# Adafruit_Speaker_Bonnet.net
KiCad netlist of a schematic drawn in EAGLE
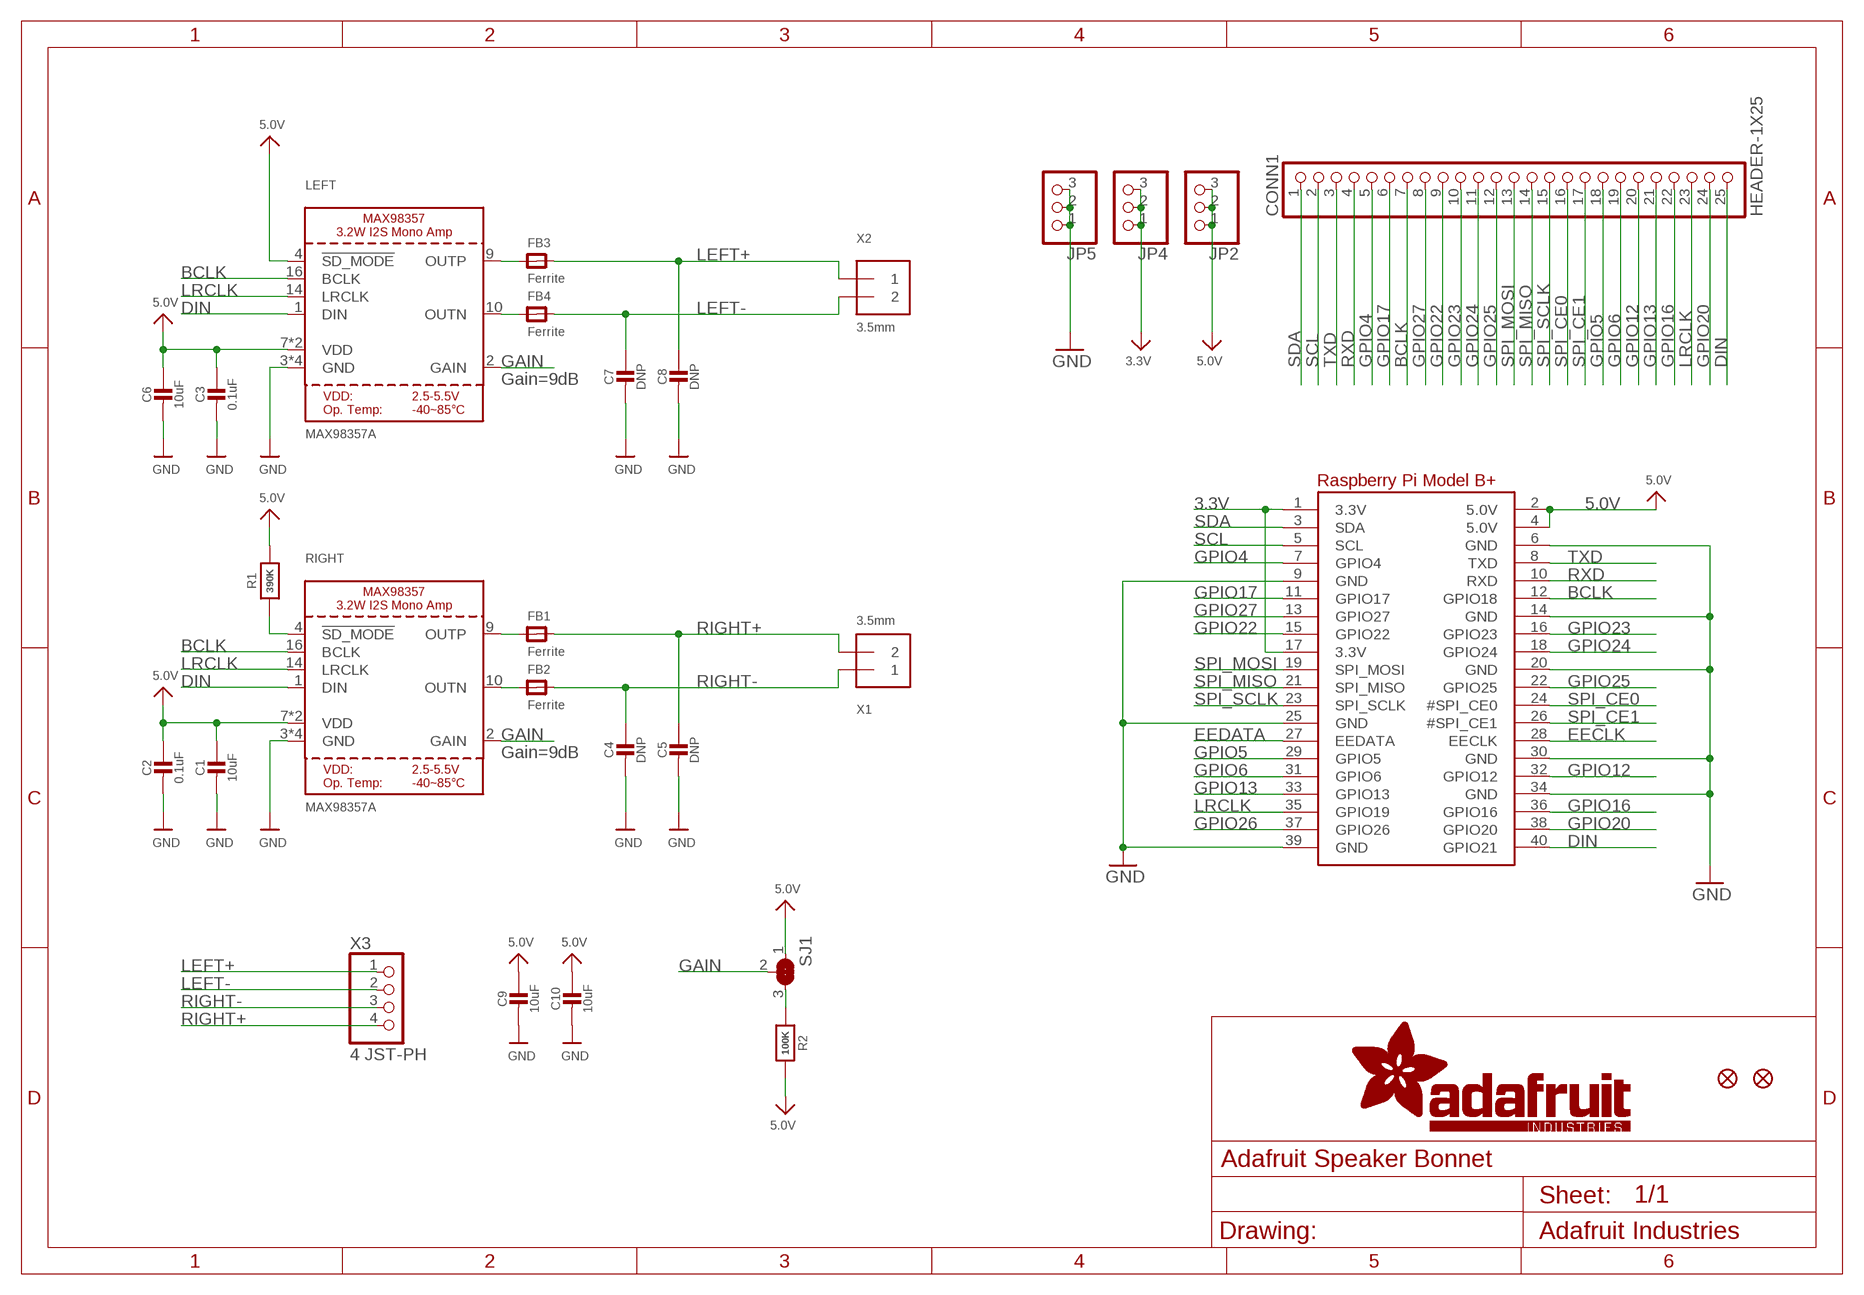
[diagram p0: schematic, sheet 1]

(export (version "E")
  (design (tool "Eeschema 10.0.6"))
  (components
    (comp (ref "C1")
      (value "10uF")
      (footprint "eagle-import:0805-NO")
      (libsource (lib "eagle-import") (part "CAP_CERAMIC0805-NOOUTLINE"))
    )
    (comp (ref "C2")
      (value "0.1uF")
      (footprint "eagle-import:0805-NO")
      (libsource (lib "eagle-import") (part "CAP_CERAMIC0805-NOOUTLINE"))
    )
    (comp (ref "C3")
      (value "0.1uF")
      (footprint "eagle-import:0805-NO")
      (libsource (lib "eagle-import") (part "CAP_CERAMIC0805-NOOUTLINE"))
    )
    (comp (ref "C4")
      (value "DNP")
      (footprint "eagle-import:0805-NO")
      (libsource (lib "eagle-import") (part "CAP_CERAMIC0805-NOOUTLINE"))
    )
    (comp (ref "C5")
      (value "DNP")
      (footprint "eagle-import:0805-NO")
      (libsource (lib "eagle-import") (part "CAP_CERAMIC0805-NOOUTLINE"))
    )
    (comp (ref "C6")
      (value "10uF")
      (footprint "eagle-import:0805-NO")
      (libsource (lib "eagle-import") (part "CAP_CERAMIC0805-NOOUTLINE"))
    )
    (comp (ref "C7")
      (value "DNP")
      (footprint "eagle-import:0805-NO")
      (libsource (lib "eagle-import") (part "CAP_CERAMIC0805-NOOUTLINE"))
    )
    (comp (ref "C8")
      (value "DNP")
      (footprint "eagle-import:0805-NO")
      (libsource (lib "eagle-import") (part "CAP_CERAMIC0805-NOOUTLINE"))
    )
    (comp (ref "C9")
      (value "10uF")
      (footprint "eagle-import:0805-NO")
      (libsource (lib "eagle-import") (part "CAP_CERAMIC0805-NOOUTLINE"))
    )
    (comp (ref "C10")
      (value "10uF")
      (footprint "eagle-import:0805-NO")
      (libsource (lib "eagle-import") (part "CAP_CERAMIC0805-NOOUTLINE"))
    )
    (comp (ref "CONN1")
      (value "HEADER-1X25")
      (footprint "eagle-import:1X25_ROUND_70MIL")
      (libsource (lib "eagle-import") (part "HEADER-1X25"))
    )
    (comp (ref "FB1")
      (value "Ferrite")
      (footprint "eagle-import:0805-NO")
      (libsource (lib "eagle-import") (part "FERRITE-0805NO"))
    )
    (comp (ref "FB2")
      (value "Ferrite")
      (footprint "eagle-import:0805-NO")
      (libsource (lib "eagle-import") (part "FERRITE-0805NO"))
    )
    (comp (ref "FB3")
      (value "Ferrite")
      (footprint "eagle-import:0805-NO")
      (libsource (lib "eagle-import") (part "FERRITE-0805NO"))
    )
    (comp (ref "FB4")
      (value "Ferrite")
      (footprint "eagle-import:0805-NO")
      (libsource (lib "eagle-import") (part "FERRITE-0805NO"))
    )
    (comp (ref "FID1")
      (value "FIDUCIAL\"\"")
      (footprint "eagle-import:FIDUCIAL_1MM")
      (libsource (lib "eagle-import") (part "FIDUCIAL{dblquote}{dblquote}"))
    )
    (comp (ref "FID2")
      (value "FIDUCIAL\"\"")
      (footprint "eagle-import:FIDUCIAL_1MM")
      (libsource (lib "eagle-import") (part "FIDUCIAL{dblquote}{dblquote}"))
    )
    (comp (ref "JP2")
      (value "HEADER-1X376MIL")
      (footprint "eagle-import:1X03_ROUND_76")
      (libsource (lib "eagle-import") (part "HEADER-1X376MIL"))
    )
    (comp (ref "JP4")
      (value "HEADER-1X376MIL")
      (footprint "eagle-import:1X03_ROUND_76")
      (libsource (lib "eagle-import") (part "HEADER-1X376MIL"))
    )
    (comp (ref "JP5")
      (value "HEADER-1X376MIL")
      (footprint "eagle-import:1X03_ROUND_76")
      (libsource (lib "eagle-import") (part "HEADER-1X376MIL"))
    )
    (comp (ref "LEFT")
      (value "MAX98357A")
      (footprint "eagle-import:QFN16_3MM")
      (libsource (lib "eagle-import") (part "AUDIOAMP_MAX98357"))
    )
    (comp (ref "R1")
      (value "390K")
      (footprint "eagle-import:0805-NO")
      (libsource (lib "eagle-import") (part "RESISTOR0805_NOOUTLINE"))
    )
    (comp (ref "R2")
      (value "100K")
      (footprint "eagle-import:0805-NO")
      (libsource (lib "eagle-import") (part "RESISTOR0805_NOOUTLINE"))
    )
    (comp (ref "RIGHT")
      (value "MAX98357A")
      (footprint "eagle-import:QFN16_3MM")
      (libsource (lib "eagle-import") (part "AUDIOAMP_MAX98357"))
    )
    (comp (ref "RPI1")
      (value "RASPBERRYPI_BPLUS_BONNETNODIM")
      (footprint "eagle-import:PI_BONNET_NODIM")
      (libsource (lib "eagle-import") (part "RASPBERRYPI_BPLUS_BONNETNODIM"))
    )
    (comp (ref "SJ1")
      (value "SOLDERJUMPER_2WAY")
      (footprint "eagle-import:SOLDERJUMPER_2WAY_OPEN_NOPASTE")
      (libsource (lib "eagle-import") (part "SOLDERJUMPER_2WAY"))
    )
    (comp (ref "X1")
      (value "3.5mm")
      (footprint "eagle-import:TERMBLOCK_1X2-3.5MM")
      (libsource (lib "eagle-import") (part "TERMBLOCK_1X2"))
    )
    (comp (ref "X2")
      (value "3.5mm")
      (footprint "eagle-import:TERMBLOCK_1X2-3.5MM")
      (libsource (lib "eagle-import") (part "TERMBLOCK_1X2"))
    )
    (comp (ref "X3")
      (value "4 JST-PH")
      (footprint "eagle-import:JSTPH4")
      (libsource (lib "eagle-import") (part "CON_JST_PH_4PIN"))
    )
  )
  (nets
    (net (code "1") (name "/BCLK") (class "Default")
      (node (ref "CONN1") (pin "7") (pinfunction "7_7") (pintype "passive"))
      (node (ref "LEFT") (pin "16") (pinfunction "BCLK_16") (pintype "bidirectional"))
      (node (ref "RIGHT") (pin "16") (pinfunction "BCLK_16") (pintype "bidirectional"))
      (node (ref "RPI1") (pin "12") (pinfunction "GPIO18_12") (pintype "bidirectional"))
    )
    (net (code "2") (name "/DIN") (class "Default")
      (node (ref "CONN1") (pin "25") (pinfunction "25_25") (pintype "passive"))
      (node (ref "LEFT") (pin "1") (pinfunction "DIN_1") (pintype "bidirectional"))
      (node (ref "RIGHT") (pin "1") (pinfunction "DIN_1") (pintype "bidirectional"))
      (node (ref "RPI1") (pin "40") (pinfunction "GPIO21_40") (pintype "bidirectional"))
    )
    (net (code "3") (name "/EECLK") (class "Default")
      (node (ref "RPI1") (pin "28") (pinfunction "EECLK_28") (pintype "bidirectional"))
    )
    (net (code "4") (name "/EEDATA") (class "Default")
      (node (ref "RPI1") (pin "27") (pinfunction "EEDATA_27") (pintype "bidirectional"))
    )
    (net (code "5") (name "/GAIN") (class "Default")
      (node (ref "LEFT") (pin "2") (pinfunction "GAIN_2") (pintype "bidirectional"))
      (node (ref "RIGHT") (pin "2") (pinfunction "GAIN_2") (pintype "bidirectional"))
      (node (ref "SJ1") (pin "2") (pinfunction "2_2") (pintype "passive"))
    )
    (net (code "6") (name "/GPIO4") (class "Default")
      (node (ref "CONN1") (pin "5") (pinfunction "5_5") (pintype "passive"))
      (node (ref "RPI1") (pin "7") (pinfunction "GPIO4_7") (pintype "bidirectional"))
    )
    (net (code "7") (name "/GPIO5") (class "Default")
      (node (ref "CONN1") (pin "18") (pinfunction "18_18") (pintype "passive"))
      (node (ref "RPI1") (pin "29") (pinfunction "GPIO5_29") (pintype "bidirectional"))
    )
    (net (code "8") (name "/GPIO6") (class "Default")
      (node (ref "CONN1") (pin "19") (pinfunction "19_19") (pintype "passive"))
      (node (ref "RPI1") (pin "31") (pinfunction "GPIO6_31") (pintype "bidirectional"))
    )
    (net (code "9") (name "/GPIO12") (class "Default")
      (node (ref "CONN1") (pin "20") (pinfunction "20_20") (pintype "passive"))
      (node (ref "RPI1") (pin "32") (pinfunction "GPIO12_32") (pintype "bidirectional"))
    )
    (net (code "10") (name "/GPIO13") (class "Default")
      (node (ref "CONN1") (pin "21") (pinfunction "21_21") (pintype "passive"))
      (node (ref "RPI1") (pin "33") (pinfunction "GPIO13_33") (pintype "bidirectional"))
    )
    (net (code "11") (name "/GPIO16") (class "Default")
      (node (ref "CONN1") (pin "22") (pinfunction "22_22") (pintype "passive"))
      (node (ref "RPI1") (pin "36") (pinfunction "GPIO16_36") (pintype "bidirectional"))
    )
    (net (code "12") (name "/GPIO17") (class "Default")
      (node (ref "CONN1") (pin "6") (pinfunction "6_6") (pintype "passive"))
      (node (ref "RPI1") (pin "11") (pinfunction "GPIO17_11") (pintype "bidirectional"))
    )
    (net (code "13") (name "/GPIO20") (class "Default")
      (node (ref "CONN1") (pin "24") (pinfunction "24_24") (pintype "passive"))
      (node (ref "RPI1") (pin "38") (pinfunction "GPIO20_38") (pintype "bidirectional"))
    )
    (net (code "14") (name "/GPIO22") (class "Default")
      (node (ref "CONN1") (pin "9") (pinfunction "9_9") (pintype "passive"))
      (node (ref "RPI1") (pin "15") (pinfunction "GPIO22_15") (pintype "bidirectional"))
    )
    (net (code "15") (name "/GPIO23") (class "Default")
      (node (ref "CONN1") (pin "10") (pinfunction "10_10") (pintype "passive"))
      (node (ref "RPI1") (pin "16") (pinfunction "GPIO23_16") (pintype "bidirectional"))
    )
    (net (code "16") (name "/GPIO24") (class "Default")
      (node (ref "CONN1") (pin "11") (pinfunction "11_11") (pintype "passive"))
      (node (ref "RPI1") (pin "18") (pinfunction "GPIO24_18") (pintype "bidirectional"))
    )
    (net (code "17") (name "/GPIO25") (class "Default")
      (node (ref "CONN1") (pin "12") (pinfunction "12_12") (pintype "passive"))
      (node (ref "RPI1") (pin "22") (pinfunction "GPIO25_22") (pintype "bidirectional"))
    )
    (net (code "18") (name "/GPIO26") (class "Default")
      (node (ref "RPI1") (pin "37") (pinfunction "GPIO26_37") (pintype "bidirectional"))
    )
    (net (code "19") (name "/GPIO27") (class "Default")
      (node (ref "CONN1") (pin "8") (pinfunction "8_8") (pintype "passive"))
      (node (ref "RPI1") (pin "13") (pinfunction "GPIO27_13") (pintype "bidirectional"))
    )
    (net (code "20") (name "/LEFT+") (class "Default")
      (node (ref "C8") (pin "1") (pinfunction "1_1") (pintype "passive"))
      (node (ref "FB3") (pin "2") (pinfunction "P$2_2") (pintype "passive"))
      (node (ref "X2") (pin "1") (pinfunction "1_1") (pintype "passive"))
      (node (ref "X3") (pin "1") (pinfunction "1_1") (pintype "passive"))
    )
    (net (code "21") (name "/LEFT-") (class "Default")
      (node (ref "C7") (pin "1") (pinfunction "1_1") (pintype "passive"))
      (node (ref "FB4") (pin "2") (pinfunction "P$2_2") (pintype "passive"))
      (node (ref "X2") (pin "2") (pinfunction "2_2") (pintype "passive"))
      (node (ref "X3") (pin "2") (pinfunction "2_2") (pintype "passive"))
    )
    (net (code "22") (name "/LRCLK") (class "Default")
      (node (ref "CONN1") (pin "23") (pinfunction "23_23") (pintype "passive"))
      (node (ref "LEFT") (pin "14") (pinfunction "LRCLK_14") (pintype "bidirectional"))
      (node (ref "RIGHT") (pin "14") (pinfunction "LRCLK_14") (pintype "bidirectional"))
      (node (ref "RPI1") (pin "35") (pinfunction "GPIO19_35") (pintype "bidirectional"))
    )
    (net (code "23") (name "/RIGHT+") (class "Default")
      (node (ref "C5") (pin "1") (pinfunction "1_1") (pintype "passive"))
      (node (ref "FB1") (pin "2") (pinfunction "P$2_2") (pintype "passive"))
      (node (ref "X1") (pin "2") (pinfunction "2_2") (pintype "passive"))
      (node (ref "X3") (pin "4") (pinfunction "4_4") (pintype "passive"))
    )
    (net (code "24") (name "/RIGHT-") (class "Default")
      (node (ref "C4") (pin "1") (pinfunction "1_1") (pintype "passive"))
      (node (ref "FB2") (pin "2") (pinfunction "P$2_2") (pintype "passive"))
      (node (ref "X1") (pin "1") (pinfunction "1_1") (pintype "passive"))
      (node (ref "X3") (pin "3") (pinfunction "3_3") (pintype "passive"))
    )
    (net (code "25") (name "/RXD") (class "Default")
      (node (ref "CONN1") (pin "4") (pinfunction "4_4") (pintype "passive"))
      (node (ref "RPI1") (pin "10") (pinfunction "RXD_10") (pintype "bidirectional"))
    )
    (net (code "26") (name "/SCL") (class "Default")
      (node (ref "CONN1") (pin "2") (pinfunction "2_2") (pintype "passive"))
      (node (ref "RPI1") (pin "5") (pinfunction "SCL_5") (pintype "bidirectional"))
    )
    (net (code "27") (name "/SDA") (class "Default")
      (node (ref "CONN1") (pin "1") (pinfunction "1_1") (pintype "passive"))
      (node (ref "RPI1") (pin "3") (pinfunction "SDA_3") (pintype "bidirectional"))
    )
    (net (code "28") (name "/SPI_CE0") (class "Default")
      (node (ref "CONN1") (pin "16") (pinfunction "16_16") (pintype "passive"))
      (node (ref "RPI1") (pin "24") (pinfunction "#SPI_CE0_24") (pintype "bidirectional"))
    )
    (net (code "29") (name "/SPI_CE1") (class "Default")
      (node (ref "CONN1") (pin "17") (pinfunction "17_17") (pintype "passive"))
      (node (ref "RPI1") (pin "26") (pinfunction "#SPI_CE1_26") (pintype "bidirectional"))
    )
    (net (code "30") (name "/SPI_MISO") (class "Default")
      (node (ref "CONN1") (pin "14") (pinfunction "14_14") (pintype "passive"))
      (node (ref "RPI1") (pin "21") (pinfunction "SPI_MISO_21") (pintype "bidirectional"))
    )
    (net (code "31") (name "/SPI_MOSI") (class "Default")
      (node (ref "CONN1") (pin "13") (pinfunction "13_13") (pintype "passive"))
      (node (ref "RPI1") (pin "19") (pinfunction "SPI_MOSI_19") (pintype "bidirectional"))
    )
    (net (code "32") (name "/SPI_SCLK") (class "Default")
      (node (ref "CONN1") (pin "15") (pinfunction "15_15") (pintype "passive"))
      (node (ref "RPI1") (pin "23") (pinfunction "SPI_SCLK_23") (pintype "bidirectional"))
    )
    (net (code "33") (name "/TXD") (class "Default")
      (node (ref "CONN1") (pin "3") (pinfunction "3_3") (pintype "passive"))
      (node (ref "RPI1") (pin "8") (pinfunction "TXD_8") (pintype "bidirectional"))
    )
    (net (code "34") (name "3.3V") (class "Default")
      (node (ref "JP4") (pin "1") (pinfunction "1_1") (pintype "passive"))
      (node (ref "JP4") (pin "2") (pinfunction "2_2") (pintype "passive"))
      (node (ref "JP4") (pin "3") (pinfunction "3_3") (pintype "passive"))
      (node (ref "RPI1") (pin "1") (pinfunction "3.3V_1") (pintype "power_in"))
      (node (ref "RPI1") (pin "17") (pinfunction "3.3V_17") (pintype "power_in"))
    )
    (net (code "35") (name "5.0V") (class "Default")
      (node (ref "C1") (pin "1") (pinfunction "1_1") (pintype "passive"))
      (node (ref "C10") (pin "1") (pinfunction "1_1") (pintype "passive"))
      (node (ref "C2") (pin "1") (pinfunction "1_1") (pintype "passive"))
      (node (ref "C3") (pin "1") (pinfunction "1_1") (pintype "passive"))
      (node (ref "C6") (pin "1") (pinfunction "1_1") (pintype "passive"))
      (node (ref "C9") (pin "1") (pinfunction "1_1") (pintype "passive"))
      (node (ref "JP2") (pin "1") (pinfunction "1_1") (pintype "passive"))
      (node (ref "JP2") (pin "2") (pinfunction "2_2") (pintype "passive"))
      (node (ref "JP2") (pin "3") (pinfunction "3_3") (pintype "passive"))
      (node (ref "LEFT") (pin "4") (pinfunction "~{SD_MODE}_4") (pintype "bidirectional"))
      (node (ref "LEFT") (pin "7") (pinfunction "VDD_7") (pintype "power_in"))
      (node (ref "LEFT") (pin "8") (pinfunction "VDD_8") (pintype "power_in"))
      (node (ref "R1") (pin "2") (pinfunction "2_2") (pintype "passive"))
      (node (ref "R2") (pin "2") (pinfunction "2_2") (pintype "passive"))
      (node (ref "RIGHT") (pin "7") (pinfunction "VDD_7") (pintype "power_in"))
      (node (ref "RIGHT") (pin "8") (pinfunction "VDD_8") (pintype "power_in"))
      (node (ref "RPI1") (pin "2") (pinfunction "5.0V_2") (pintype "power_in"))
      (node (ref "RPI1") (pin "4") (pinfunction "5.0V_4") (pintype "power_in"))
      (node (ref "SJ1") (pin "1") (pinfunction "1_1") (pintype "passive"))
    )
    (net (code "36") (name "GND") (class "Default")
      (node (ref "C1") (pin "2") (pinfunction "2_2") (pintype "passive"))
      (node (ref "C10") (pin "2") (pinfunction "2_2") (pintype "passive"))
      (node (ref "C2") (pin "2") (pinfunction "2_2") (pintype "passive"))
      (node (ref "C3") (pin "2") (pinfunction "2_2") (pintype "passive"))
      (node (ref "C4") (pin "2") (pinfunction "2_2") (pintype "passive"))
      (node (ref "C5") (pin "2") (pinfunction "2_2") (pintype "passive"))
      (node (ref "C6") (pin "2") (pinfunction "2_2") (pintype "passive"))
      (node (ref "C7") (pin "2") (pinfunction "2_2") (pintype "passive"))
      (node (ref "C8") (pin "2") (pinfunction "2_2") (pintype "passive"))
      (node (ref "C9") (pin "2") (pinfunction "2_2") (pintype "passive"))
      (node (ref "JP5") (pin "1") (pinfunction "1_1") (pintype "passive"))
      (node (ref "JP5") (pin "2") (pinfunction "2_2") (pintype "passive"))
      (node (ref "JP5") (pin "3") (pinfunction "3_3") (pintype "passive"))
      (node (ref "LEFT") (pin "11") (pinfunction "GND_11") (pintype "power_in"))
      (node (ref "LEFT") (pin "15") (pinfunction "GND_15") (pintype "power_in"))
      (node (ref "LEFT") (pin "3") (pinfunction "GND_3") (pintype "power_in"))
      (node (ref "LEFT") (pin "THERMAL") (pinfunction "GND_THERMAL") (pintype "power_in"))
      (node (ref "RIGHT") (pin "11") (pinfunction "GND_11") (pintype "power_in"))
      (node (ref "RIGHT") (pin "15") (pinfunction "GND_15") (pintype "power_in"))
      (node (ref "RIGHT") (pin "3") (pinfunction "GND_3") (pintype "power_in"))
      (node (ref "RIGHT") (pin "THERMAL") (pinfunction "GND_THERMAL") (pintype "power_in"))
      (node (ref "RPI1") (pin "14") (pinfunction "GND_14") (pintype "power_in"))
      (node (ref "RPI1") (pin "20") (pinfunction "GND_20") (pintype "power_in"))
      (node (ref "RPI1") (pin "25") (pinfunction "GND_25") (pintype "power_in"))
      (node (ref "RPI1") (pin "30") (pinfunction "GND_30") (pintype "power_in"))
      (node (ref "RPI1") (pin "34") (pinfunction "GND_34") (pintype "power_in"))
      (node (ref "RPI1") (pin "39") (pinfunction "GND_39") (pintype "power_in"))
      (node (ref "RPI1") (pin "6") (pinfunction "GND_6") (pintype "power_in"))
      (node (ref "RPI1") (pin "9") (pinfunction "GND_9") (pintype "power_in"))
    )
    (net (code "37") (name "Net-(FB1-P$1)") (class "Default")
      (node (ref "FB1") (pin "1") (pinfunction "P$1_1") (pintype "passive"))
      (node (ref "RIGHT") (pin "9") (pinfunction "OUTP_9") (pintype "output"))
    )
    (net (code "38") (name "Net-(FB2-P$1)") (class "Default")
      (node (ref "FB2") (pin "1") (pinfunction "P$1_1") (pintype "passive"))
      (node (ref "RIGHT") (pin "10") (pinfunction "OUTN_10") (pintype "output"))
    )
    (net (code "39") (name "Net-(FB3-P$1)") (class "Default")
      (node (ref "FB3") (pin "1") (pinfunction "P$1_1") (pintype "passive"))
      (node (ref "LEFT") (pin "9") (pinfunction "OUTP_9") (pintype "output"))
    )
    (net (code "40") (name "Net-(FB4-P$1)") (class "Default")
      (node (ref "FB4") (pin "1") (pinfunction "P$1_1") (pintype "passive"))
      (node (ref "LEFT") (pin "10") (pinfunction "OUTN_10") (pintype "output"))
    )
    (net (code "41") (name "Net-(R2-Pad1)") (class "Default")
      (node (ref "R2") (pin "1") (pinfunction "1_1") (pintype "passive"))
      (node (ref "SJ1") (pin "3") (pinfunction "3_3") (pintype "passive"))
    )
    (net (code "42") (name "Net-(RIGHT-~{SD_MODE})") (class "Default")
      (node (ref "R1") (pin "1") (pinfunction "1_1") (pintype "passive"))
      (node (ref "RIGHT") (pin "4") (pinfunction "~{SD_MODE}_4") (pintype "bidirectional"))
    )
  )
)
